# BITSv4.net
KiCad netlist of a schematic drawn in EAGLE
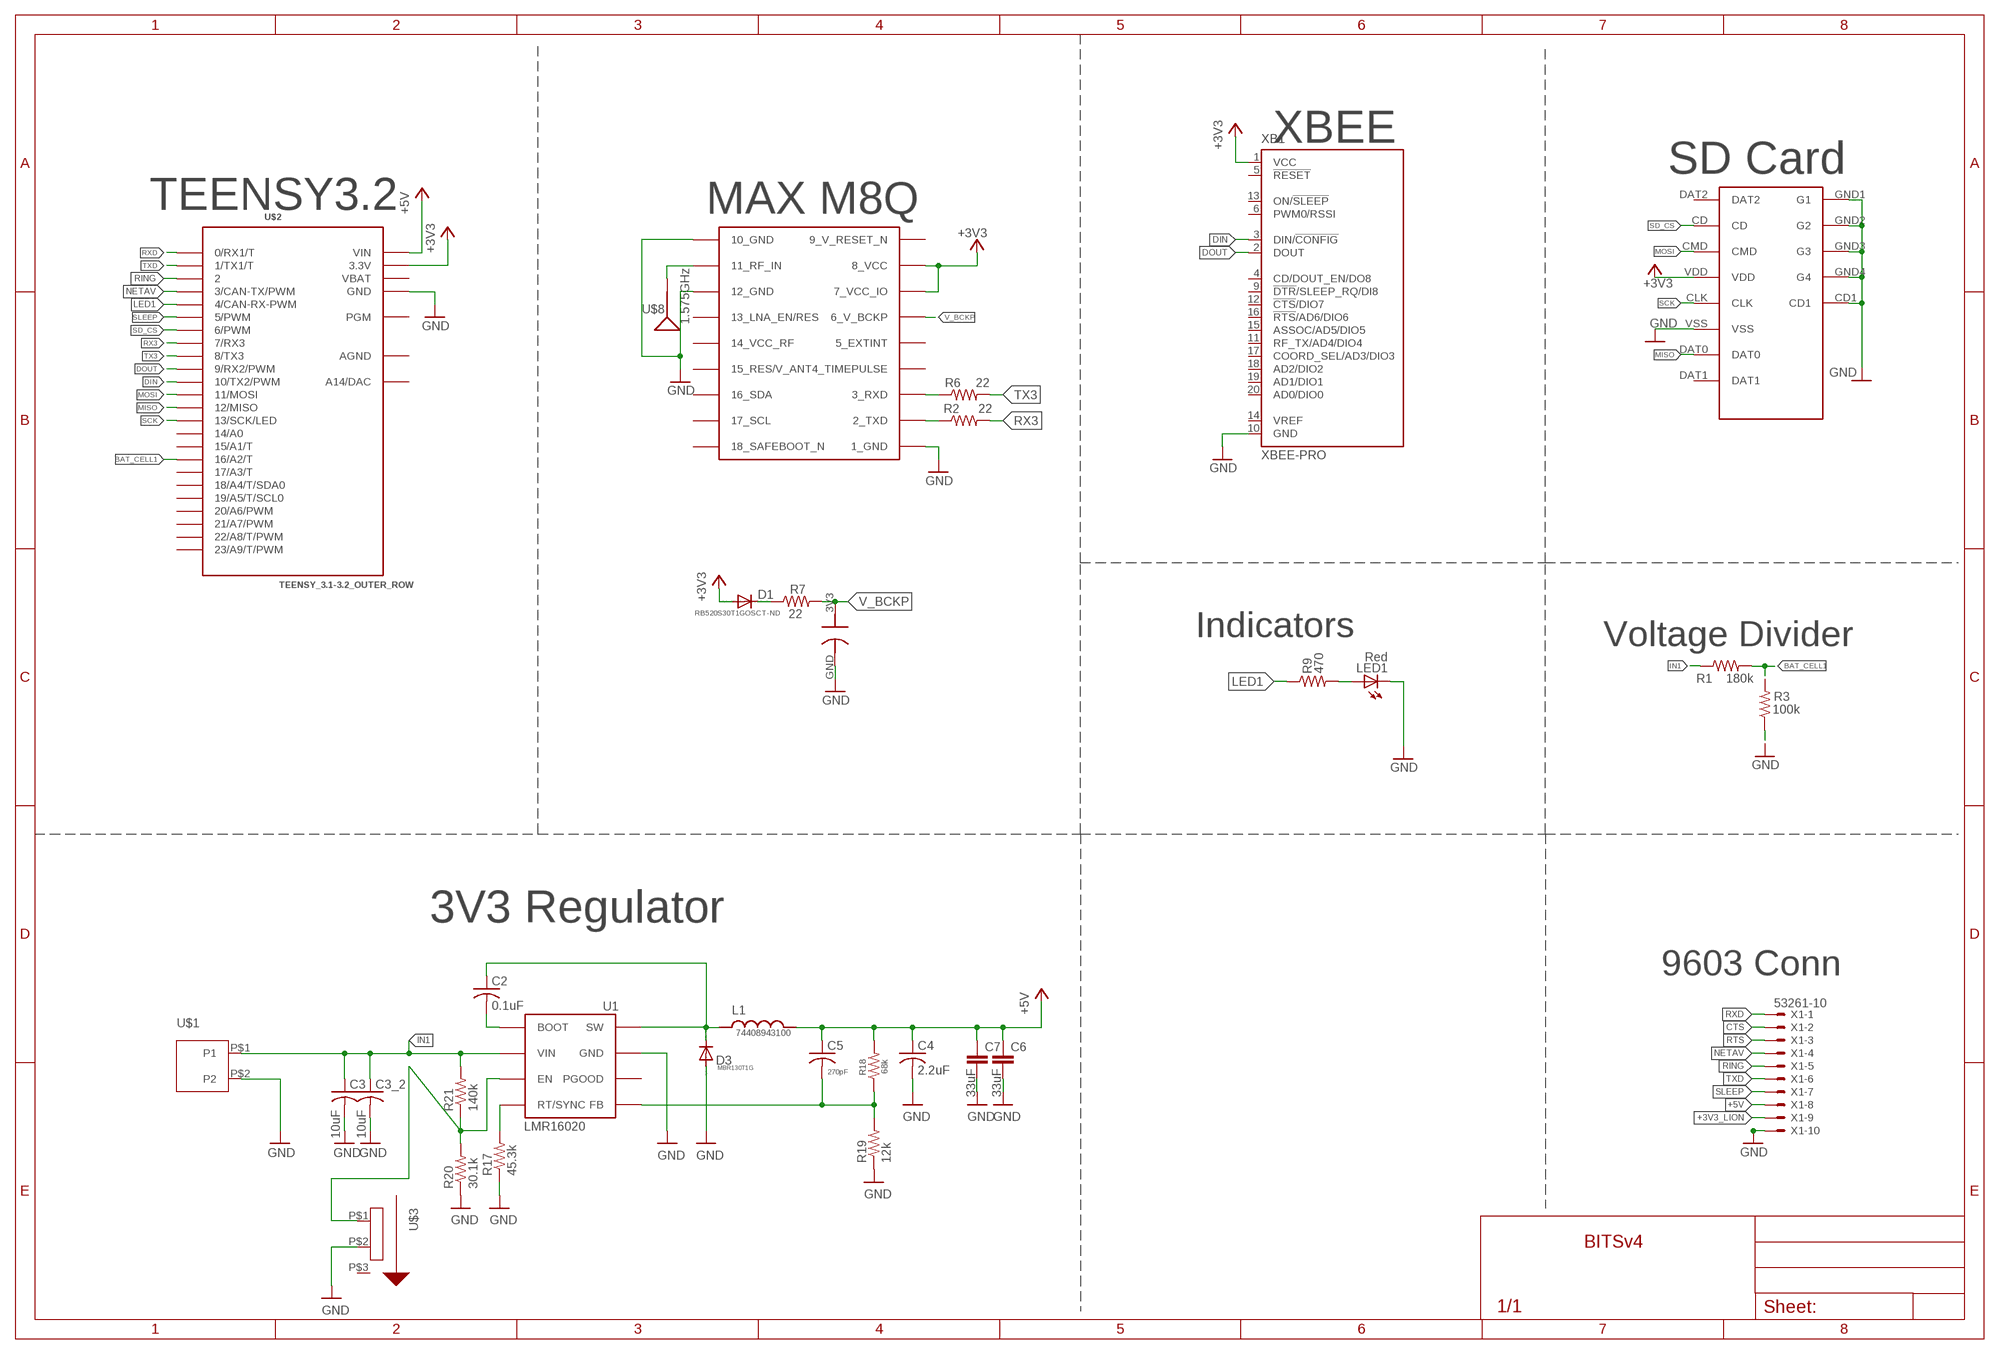
[diagram p0: schematic, sheet 1]

(export (version "E")
  (design (tool "Eeschema 10.0.6"))
  (components
    (comp (ref "C1")
      (value "0.2F")
      (footprint "eagle-import:ELNASUPERCAP")
      (libsource (lib "eagle-import") (part "DCK-3R3E204T614-E"))
    )
    (comp (ref "C2")
      (value "0.1uF")
      (footprint "eagle-import:C0603")
      (libsource (lib "eagle-import") (part "resistor_C-USC0603"))
    )
    (comp (ref "C3")
      (value "10uF")
      (footprint "eagle-import:C0805")
      (libsource (lib "eagle-import") (part "C-USC0805"))
    )
    (comp (ref "C3_2")
      (value "10uF")
      (footprint "eagle-import:C0805")
      (libsource (lib "eagle-import") (part "C-USC0805"))
    )
    (comp (ref "C4")
      (value "2.2uF")
      (footprint "eagle-import:C0603")
      (libsource (lib "eagle-import") (part "C-USC0603"))
    )
    (comp (ref "C5")
      (value "270pF")
      (footprint "eagle-import:C0402")
      (libsource (lib "eagle-import") (part "C-USC0402"))
    )
    (comp (ref "C6")
      (value "33uF")
      (footprint "eagle-import:C050-024X044")
      (libsource (lib "eagle-import") (part "C-EU050-024X044"))
    )
    (comp (ref "C7")
      (value "33uF")
      (footprint "eagle-import:C050-024X044")
      (libsource (lib "eagle-import") (part "C-EU050-024X044"))
    )
    (comp (ref "D1")
      (value "RB520S30T1GOSCT-ND")
      (footprint "eagle-import:SOD523")
      (libsource (lib "eagle-import") (part "DIODE-SOD523"))
    )
    (comp (ref "D3")
      (value "MBR130T1G")
      (footprint "eagle-import:SOD-123_MINI-SMA")
      (libsource (lib "eagle-import") (part "CGRM400-G1"))
    )
    (comp (ref "L1")
      (value "74408943100")
      (footprint "eagle-import:74408943100")
      (libsource (lib "eagle-import") (part "74408943100"))
    )
    (comp (ref "LED1")
      (value "Red")
      (footprint "eagle-import:CHIP-LED0603")
      (libsource (lib "eagle-import") (part "LEDCHIP-LED0603"))
    )
    (comp (ref "R1")
      (value "180k")
      (footprint "eagle-import:R0603")
      (libsource (lib "eagle-import") (part "resistor_R-US_R0603"))
    )
    (comp (ref "R2")
      (value "22")
      (footprint "eagle-import:R0603")
      (libsource (lib "eagle-import") (part "R-US_R0603"))
    )
    (comp (ref "R3")
      (value "100k")
      (footprint "eagle-import:R0603")
      (libsource (lib "eagle-import") (part "resistor_R-US_R0603"))
    )
    (comp (ref "R6")
      (value "22")
      (footprint "eagle-import:R0603")
      (libsource (lib "eagle-import") (part "R-US_R0603"))
    )
    (comp (ref "R7")
      (value "22")
      (footprint "eagle-import:R0603")
      (libsource (lib "eagle-import") (part "R-US_R0603"))
    )
    (comp (ref "R9")
      (value "470")
      (footprint "eagle-import:R0603")
      (libsource (lib "eagle-import") (part "resistor_R-US_R0603"))
    )
    (comp (ref "R17")
      (value "45.3k")
      (footprint "eagle-import:R0603")
      (libsource (lib "eagle-import") (part "resistor_R-US_R0603"))
    )
    (comp (ref "R18")
      (value "68k")
      (footprint "eagle-import:R0603")
      (libsource (lib "eagle-import") (part "resistor_R-US_R0603"))
    )
    (comp (ref "R19")
      (value "12k")
      (footprint "eagle-import:R0603")
      (libsource (lib "eagle-import") (part "resistor_R-US_R0603"))
    )
    (comp (ref "R20")
      (value "30.1k")
      (footprint "eagle-import:R0603")
      (libsource (lib "eagle-import") (part "resistor_R-US_R0603"))
    )
    (comp (ref "R21")
      (value "140k")
      (footprint "eagle-import:R0603")
      (libsource (lib "eagle-import") (part "resistor_R-US_R0603"))
    )
    (comp (ref "U$1")
      (value "559350210")
      (footprint "eagle-import:559350210")
      (libsource (lib "eagle-import") (part "559350210"))
    )
    (comp (ref "U$2")
      (value "TEENSY_3.1-3.2_OUTER_ROW")
      (footprint "eagle-import:TEENSY_3.0-3.2&LC_OUTER_ROW")
      (libsource (lib "eagle-import") (part "TEENSY_3.1-3.2_OUTER_ROW"))
    )
    (comp (ref "U$3")
      (value "CL-SB-12B-01")
      (footprint "eagle-import:CL-SB-12B-01")
      (libsource (lib "eagle-import") (part "CL-SB-12B-01"))
    )
    (comp (ref "U$4")
      (value "MICRO_SD")
      (footprint "eagle-import:MICRO_SD_HINGED")
      (libsource (lib "eagle-import") (part "MICRO_SD"))
    )
    (comp (ref "U$7")
      (value "MAX-M8")
      (footprint "eagle-import:MAX-M8")
      (libsource (lib "eagle-import") (part "MAX-M8"))
    )
    (comp (ref "U$8")
      (value "1.575GHz")
      (footprint "eagle-import:SPARKFUN-GPS_ANT-GPS-2X7MM")
      (libsource (lib "eagle-import") (part "SPARKFUN-GPS_ANTENNAGPS-2X7MM"))
    )
    (comp (ref "U1")
      (value "LMR16020")
      (footprint "eagle-import:SO8")
      (libsource (lib "eagle-import") (part "LMR16020"))
    )
    (comp (ref "X1")
      (value "53261-10")
      (footprint "eagle-import:53261-10")
      (fields (field (name "MF") "MOLEX"))
      (libsource (lib "eagle-import") (part "53?-10261"))
    )
    (comp (ref "XB1")
      (value "XBEE-PRO")
      (footprint "eagle-import:XBEE-PRO")
      (libsource (lib "eagle-import") (part "XBEE-PRO"))
    )
  )
  (nets
    (net (code "1") (name "+3V3") (class "Default")
      (node (ref "D1") (pin "A") (pinfunction "A_A") (pintype "passive"))
      (node (ref "U$2") (pin "3.3V") (pinfunction "3.3V_3.3V") (pintype "power_in"))
      (node (ref "U$2") (pin "3.3V1") (pinfunction "3.3V_3.3V1") (pintype "power_in"))
      (node (ref "U$4") (pin "VDD") (pinfunction "VDD_VDD") (pintype "bidirectional"))
      (node (ref "U$7") (pin "7_VCC_IO") (pinfunction "7_VCC_IO_7_VCC_IO") (pintype "power_in"))
      (node (ref "U$7") (pin "8_VCC") (pinfunction "8_VCC_8_VCC") (pintype "power_in"))
      (node (ref "XB1") (pin "1") (pinfunction "VCC_1") (pintype "power_in"))
    )
    (net (code "2") (name "+3V3_LION") (class "Default")
      (node (ref "X1") (pin "9") (pinfunction "S_9") (pintype "passive"))
    )
    (net (code "3") (name "+5V") (class "Default")
      (node (ref "C4") (pin "1") (pinfunction "1_1") (pintype "passive"))
      (node (ref "C5") (pin "1") (pinfunction "1_1") (pintype "passive"))
      (node (ref "C6") (pin "1") (pinfunction "1_1") (pintype "passive"))
      (node (ref "C7") (pin "1") (pinfunction "1_1") (pintype "passive"))
      (node (ref "L1") (pin "P$2") (pinfunction "P$2_P$2") (pintype "bidirectional"))
      (node (ref "R18") (pin "2") (pinfunction "2_2") (pintype "passive"))
      (node (ref "U$2") (pin "VIN") (pinfunction "VIN_VIN") (pintype "power_in"))
      (node (ref "X1") (pin "8") (pinfunction "S_8") (pintype "passive"))
    )
    (net (code "4") (name "/9_V_RESET_N") (class "Default")
      (node (ref "U$7") (pin "9_RESET_N") (pinfunction "9_V_RESET_N_9_RESET_N") (pintype "power_in"))
    )
    (net (code "5") (name "/AGND") (class "Default")
      (node (ref "U$2") (pin "AGND") (pinfunction "AGND_AGND") (pintype "power_in"))
    )
    (net (code "6") (name "/VBAT") (class "Default")
      (node (ref "U$2") (pin "VBAT") (pinfunction "VBAT_VBAT") (pintype "power_in"))
    )
    (net (code "7") (name "BAT_CELL1") (class "Default")
      (node (ref "R1") (pin "2") (pinfunction "2_2") (pintype "passive"))
      (node (ref "R3") (pin "2") (pinfunction "2_2") (pintype "passive"))
      (node (ref "U$2") (pin "16/A2") (pinfunction "16/A2/T_16/A2") (pintype "bidirectional"))
    )
    (net (code "8") (name "CTS") (class "Default")
      (node (ref "X1") (pin "2") (pinfunction "S_2") (pintype "passive"))
    )
    (net (code "9") (name "DIN") (class "Default")
      (node (ref "U$2") (pin "10") (pinfunction "10/TX2/PWM_10") (pintype "bidirectional"))
      (node (ref "XB1") (pin "3") (pinfunction "DIN/~{CONFIG}_3") (pintype "input"))
    )
    (net (code "10") (name "DOUT") (class "Default")
      (node (ref "U$2") (pin "9") (pinfunction "9/RX2/PWM_9") (pintype "bidirectional"))
      (node (ref "XB1") (pin "2") (pinfunction "DOUT_2") (pintype "output"))
    )
    (net (code "11") (name "GND") (class "Default")
      (node (ref "C1") (pin "GND") (pinfunction "GND_GND") (pintype "bidirectional"))
      (node (ref "C3") (pin "2") (pinfunction "2_2") (pintype "passive"))
      (node (ref "C3_2") (pin "2") (pinfunction "2_2") (pintype "passive"))
      (node (ref "C4") (pin "2") (pinfunction "2_2") (pintype "passive"))
      (node (ref "C6") (pin "2") (pinfunction "2_2") (pintype "passive"))
      (node (ref "C7") (pin "2") (pinfunction "2_2") (pintype "passive"))
      (node (ref "D3") (pin "A") (pinfunction "A_A") (pintype "passive"))
      (node (ref "LED1") (pin "C") (pinfunction "C_C") (pintype "passive"))
      (node (ref "R17") (pin "1") (pinfunction "1_1") (pintype "passive"))
      (node (ref "R19") (pin "1") (pinfunction "1_1") (pintype "passive"))
      (node (ref "R20") (pin "1") (pinfunction "1_1") (pintype "passive"))
      (node (ref "R3") (pin "1") (pinfunction "1_1") (pintype "passive"))
      (node (ref "U$1") (pin "P$2") (pinfunction "P2_P$2") (pintype "bidirectional"))
      (node (ref "U$2") (pin "GND") (pinfunction "GND_GND") (pintype "power_in"))
      (node (ref "U$2") (pin "GND1") (pinfunction "GND_GND1") (pintype "power_in"))
      (node (ref "U$3") (pin "P$2") (pinfunction "P2_P$2") (pintype "bidirectional"))
      (node (ref "U$4") (pin "CD1") (pinfunction "CD1_CD1") (pintype "bidirectional"))
      (node (ref "U$4") (pin "GND1") (pinfunction "G1_GND1") (pintype "bidirectional"))
      (node (ref "U$4") (pin "GND2") (pinfunction "G2_GND2") (pintype "bidirectional"))
      (node (ref "U$4") (pin "GND3") (pinfunction "G3_GND3") (pintype "bidirectional"))
      (node (ref "U$4") (pin "GND4") (pinfunction "G4_GND4") (pintype "bidirectional"))
      (node (ref "U$4") (pin "VSS") (pinfunction "VSS_VSS") (pintype "bidirectional"))
      (node (ref "U$7") (pin "10_GND") (pinfunction "10_GND_10_GND") (pintype "power_in"))
      (node (ref "U$7") (pin "12_GND") (pinfunction "12_GND_12_GND") (pintype "power_in"))
      (node (ref "U$7") (pin "1_GND") (pinfunction "1_GND_1_GND") (pintype "power_in"))
      (node (ref "U1") (pin "P$7") (pinfunction "GND_P$7") (pintype "bidirectional"))
      (node (ref "U1") (pin "PAD") (pinfunction "GND_PAD") (pintype "bidirectional"))
      (node (ref "X1") (pin "10") (pinfunction "S_10") (pintype "passive"))
      (node (ref "XB1") (pin "10") (pinfunction "GND_10") (pintype "power_in"))
    )
    (net (code "12") (name "IN1") (class "Default")
      (node (ref "C3") (pin "1") (pinfunction "1_1") (pintype "passive"))
      (node (ref "C3_2") (pin "1") (pinfunction "1_1") (pintype "passive"))
      (node (ref "R1") (pin "1") (pinfunction "1_1") (pintype "passive"))
      (node (ref "R21") (pin "2") (pinfunction "2_2") (pintype "passive"))
      (node (ref "U$1") (pin "P$1") (pinfunction "P1_P$1") (pintype "bidirectional"))
      (node (ref "U1") (pin "P$2") (pinfunction "VIN_P$2") (pintype "bidirectional"))
    )
    (net (code "13") (name "LED1") (class "Default")
      (node (ref "R9") (pin "1") (pinfunction "1_1") (pintype "passive"))
      (node (ref "U$2") (pin "4") (pinfunction "4/CAN-RX-PWM_4") (pintype "bidirectional"))
    )
    (net (code "14") (name "MISO") (class "Default")
      (node (ref "U$2") (pin "12") (pinfunction "12/MISO_12") (pintype "bidirectional"))
      (node (ref "U$4") (pin "DAT0") (pinfunction "DAT0_DAT0") (pintype "bidirectional"))
    )
    (net (code "15") (name "MOSI") (class "Default")
      (node (ref "U$2") (pin "11") (pinfunction "11/MOSI_11") (pintype "bidirectional"))
      (node (ref "U$4") (pin "CMD") (pinfunction "CMD_CMD") (pintype "bidirectional"))
    )
    (net (code "16") (name "NETAV") (class "Default")
      (node (ref "U$2") (pin "3") (pinfunction "3/CAN-TX/PWM_3") (pintype "bidirectional"))
      (node (ref "X1") (pin "4") (pinfunction "S_4") (pintype "passive"))
    )
    (net (code "17") (name "Net-(D1-PadC)") (class "Default")
      (node (ref "D1") (pin "C") (pinfunction "C_C") (pintype "passive"))
      (node (ref "R7") (pin "1") (pinfunction "1_1") (pintype "passive"))
    )
    (net (code "18") (name "Net-(LED1-PadA)") (class "Default")
      (node (ref "LED1") (pin "A") (pinfunction "A_A") (pintype "passive"))
      (node (ref "R9") (pin "2") (pinfunction "2_2") (pintype "passive"))
    )
    (net (code "19") (name "Net-(R2-Pad1)") (class "Default")
      (node (ref "R2") (pin "1") (pinfunction "1_1") (pintype "passive"))
      (node (ref "U$7") (pin "2_TXD") (pinfunction "2_TXD_2_TXD") (pintype "bidirectional"))
    )
    (net (code "20") (name "Net-(R6-Pad1)") (class "Default")
      (node (ref "R6") (pin "1") (pinfunction "1_1") (pintype "passive"))
      (node (ref "U$7") (pin "3_RXD") (pinfunction "3_RXD_3_RXD") (pintype "bidirectional"))
    )
    (net (code "21") (name "Net-(U$3-P1)") (class "Default")
      (node (ref "R20") (pin "2") (pinfunction "2_2") (pintype "passive"))
      (node (ref "R21") (pin "1") (pinfunction "1_1") (pintype "passive"))
      (node (ref "U$3") (pin "P$1") (pinfunction "P1_P$1") (pintype "bidirectional"))
      (node (ref "U1") (pin "P$3") (pinfunction "EN_P$3") (pintype "bidirectional"))
    )
    (net (code "22") (name "Net-(U$8-SIGNAL)") (class "Default")
      (node (ref "U$7") (pin "11_RF_IN") (pinfunction "11_RF_IN_11_RF_IN") (pintype "bidirectional"))
      (node (ref "U$8") (pin "1") (pinfunction "SIGNAL_1") (pintype "bidirectional"))
    )
    (net (code "23") (name "Net-(U1-BOOT)") (class "Default")
      (node (ref "C2") (pin "2") (pinfunction "2_2") (pintype "passive"))
      (node (ref "U1") (pin "P$1") (pinfunction "BOOT_P$1") (pintype "bidirectional"))
    )
    (net (code "24") (name "Net-(U1-FB)") (class "Default")
      (node (ref "C5") (pin "2") (pinfunction "2_2") (pintype "passive"))
      (node (ref "R18") (pin "1") (pinfunction "1_1") (pintype "passive"))
      (node (ref "R19") (pin "2") (pinfunction "2_2") (pintype "passive"))
      (node (ref "U1") (pin "P$5") (pinfunction "FB_P$5") (pintype "bidirectional"))
    )
    (net (code "25") (name "Net-(U1-RT{slash}SYNC)") (class "Default")
      (node (ref "R17") (pin "2") (pinfunction "2_2") (pintype "passive"))
      (node (ref "U1") (pin "P$4") (pinfunction "RT/SYNC_P$4") (pintype "bidirectional"))
    )
    (net (code "26") (name "Net-(U1-SW)") (class "Default")
      (node (ref "C2") (pin "1") (pinfunction "1_1") (pintype "passive"))
      (node (ref "D3") (pin "C") (pinfunction "C_C") (pintype "passive"))
      (node (ref "L1") (pin "P$1") (pinfunction "P$1_P$1") (pintype "bidirectional"))
      (node (ref "U1") (pin "P$8") (pinfunction "SW_P$8") (pintype "bidirectional"))
    )
    (net (code "27") (name "RING") (class "Default")
      (node (ref "U$2") (pin "2") (pinfunction "2_2") (pintype "bidirectional"))
      (node (ref "X1") (pin "5") (pinfunction "S_5") (pintype "passive"))
    )
    (net (code "28") (name "RTS") (class "Default")
      (node (ref "X1") (pin "3") (pinfunction "S_3") (pintype "passive"))
    )
    (net (code "29") (name "RX3") (class "Default")
      (node (ref "R2") (pin "2") (pinfunction "2_2") (pintype "passive"))
      (node (ref "U$2") (pin "7") (pinfunction "7/RX3_7") (pintype "bidirectional"))
    )
    (net (code "30") (name "RXD") (class "Default")
      (node (ref "U$2") (pin "0") (pinfunction "0/RX1/T_0") (pintype "bidirectional"))
      (node (ref "X1") (pin "1") (pinfunction "S_1") (pintype "passive"))
    )
    (net (code "31") (name "SCK") (class "Default")
      (node (ref "U$2") (pin "13") (pinfunction "13/SCK/LED_13") (pintype "bidirectional"))
      (node (ref "U$4") (pin "CLK") (pinfunction "CLK_CLK") (pintype "bidirectional"))
    )
    (net (code "32") (name "SD_CS") (class "Default")
      (node (ref "U$2") (pin "6") (pinfunction "6/PWM_6") (pintype "bidirectional"))
      (node (ref "U$4") (pin "CD") (pinfunction "CD_CD") (pintype "bidirectional"))
    )
    (net (code "33") (name "SLEEP") (class "Default")
      (node (ref "U$2") (pin "5") (pinfunction "5/PWM_5") (pintype "bidirectional"))
      (node (ref "X1") (pin "7") (pinfunction "S_7") (pintype "passive"))
    )
    (net (code "34") (name "TX3") (class "Default")
      (node (ref "R6") (pin "2") (pinfunction "2_2") (pintype "passive"))
      (node (ref "U$2") (pin "8") (pinfunction "8/TX3_8") (pintype "bidirectional"))
    )
    (net (code "35") (name "TXD") (class "Default")
      (node (ref "U$2") (pin "1") (pinfunction "1/TX1/T_1") (pintype "bidirectional"))
      (node (ref "X1") (pin "6") (pinfunction "S_6") (pintype "passive"))
    )
    (net (code "36") (name "V_BCKP") (class "Default")
      (node (ref "C1") (pin "3V3") (pinfunction "3V3_3V3") (pintype "bidirectional"))
      (node (ref "R7") (pin "2") (pinfunction "2_2") (pintype "passive"))
      (node (ref "U$7") (pin "6_V_BCKP") (pinfunction "6_V_BCKP_6_V_BCKP") (pintype "bidirectional"))
    )
    (net (code "37") (name "unconnected-(U$2-15{slash}A1{slash}T-Pad15{slash}A1)") (class "Default")
      (node (ref "U$2") (pin "15/A1") (pinfunction "15/A1/T_15/A1") (pintype "bidirectional"))
    )
    (net (code "38") (name "unconnected-(U$2-17{slash}A3{slash}T-Pad17{slash}A3)") (class "Default")
      (node (ref "U$2") (pin "17/A3") (pinfunction "17/A3/T_17/A3") (pintype "bidirectional"))
    )
    (net (code "39") (name "unconnected-(U$2-18{slash}A4{slash}T{slash}SDA0-Pad18{slash}A4)") (class "Default")
      (node (ref "U$2") (pin "18/A4") (pinfunction "18/A4/T/SDA0_18/A4") (pintype "bidirectional"))
    )
    (net (code "40") (name "unconnected-(U$2-19{slash}A5{slash}T{slash}SCL0-Pad19{slash}A5)") (class "Default")
      (node (ref "U$2") (pin "19/A5") (pinfunction "19/A5/T/SCL0_19/A5") (pintype "bidirectional"))
    )
    (net (code "41") (name "unconnected-(U$2-20{slash}A6{slash}PWM-Pad20{slash}A6)") (class "Default")
      (node (ref "U$2") (pin "20/A6") (pinfunction "20/A6/PWM_20/A6") (pintype "bidirectional"))
    )
    (net (code "42") (name "unconnected-(U$2-21{slash}A7{slash}PWM-Pad21{slash}A7)") (class "Default")
      (node (ref "U$2") (pin "21/A7") (pinfunction "21/A7/PWM_21/A7") (pintype "bidirectional"))
    )
    (net (code "43") (name "unconnected-(U$2-22{slash}A8{slash}T{slash}PWM-Pad22{slash}A8)") (class "Default")
      (node (ref "U$2") (pin "22/A8") (pinfunction "22/A8/T/PWM_22/A8") (pintype "bidirectional"))
    )
    (net (code "44") (name "unconnected-(U$2-23{slash}A9{slash}T{slash}PWM-Pad23{slash}A9)") (class "Default")
      (node (ref "U$2") (pin "23/A9") (pinfunction "23/A9/T/PWM_23/A9") (pintype "bidirectional"))
    )
    (net (code "45") (name "unconnected-(U$2-A14{slash}DAC-PadRESET{slash}DAC)") (class "Default")
      (node (ref "U$2") (pin "RESET/DAC") (pinfunction "A14/DAC_RESET/DAC") (pintype "bidirectional"))
    )
    (net (code "46") (name "unconnected-(U$2-Pad14{slash}A0)") (class "Default")
      (node (ref "U$2") (pin "14/A0") (pinfunction "14/A0_14/A0") (pintype "bidirectional"))
    )
    (net (code "47") (name "unconnected-(U$2-PadPGM)") (class "Default")
      (node (ref "U$2") (pin "PGM") (pinfunction "PGM_PGM") (pintype "bidirectional"))
    )
    (net (code "48") (name "unconnected-(U$3-P3-PadP$3)") (class "Default")
      (node (ref "U$3") (pin "P$3") (pinfunction "P3_P$3") (pintype "bidirectional"))
    )
    (net (code "49") (name "unconnected-(U$4-PadDAT1)") (class "Default")
      (node (ref "U$4") (pin "DAT1") (pinfunction "DAT1_DAT1") (pintype "bidirectional"))
    )
    (net (code "50") (name "unconnected-(U$4-PadDAT2)") (class "Default")
      (node (ref "U$4") (pin "DAT2") (pinfunction "DAT2_DAT2") (pintype "bidirectional"))
    )
    (net (code "51") (name "unconnected-(U$7-13_LNA_EN{slash}RES-Pad13_LNA_EN)") (class "Default")
      (node (ref "U$7") (pin "13_LNA_EN") (pinfunction "13_LNA_EN/RES_13_LNA_EN") (pintype "bidirectional"))
    )
    (net (code "52") (name "unconnected-(U$7-15_RES{slash}V_ANT-Pad15_V_ANT{slash}RESERVED)") (class "Default")
      (node (ref "U$7") (pin "15_V_ANT/RESERVED") (pinfunction "15_RES/V_ANT_15_V_ANT/RESERVED") (pintype "bidirectional"))
    )
    (net (code "53") (name "unconnected-(U$7-Pad4_TIMEPULSE)") (class "Default")
      (node (ref "U$7") (pin "4_TIMEPULSE") (pinfunction "4_TIMEPULSE_4_TIMEPULSE") (pintype "bidirectional"))
    )
    (net (code "54") (name "unconnected-(U$7-Pad5_EXTINT)") (class "Default")
      (node (ref "U$7") (pin "5_EXTINT") (pinfunction "5_EXTINT_5_EXTINT") (pintype "bidirectional"))
    )
    (net (code "55") (name "unconnected-(U$7-Pad14_VCC_RF)") (class "Default")
      (node (ref "U$7") (pin "14_VCC_RF") (pinfunction "14_VCC_RF_14_VCC_RF") (pintype "bidirectional"))
    )
    (net (code "56") (name "unconnected-(U$7-Pad16_SDA)") (class "Default")
      (node (ref "U$7") (pin "16_SDA") (pinfunction "16_SDA_16_SDA") (pintype "bidirectional"))
    )
    (net (code "57") (name "unconnected-(U$7-Pad17_SCL)") (class "Default")
      (node (ref "U$7") (pin "17_SCL") (pinfunction "17_SCL_17_SCL") (pintype "bidirectional"))
    )
    (net (code "58") (name "unconnected-(U$7-Pad18_SAFEBOOT_N)") (class "Default")
      (node (ref "U$7") (pin "18_SAFEBOOT_N") (pinfunction "18_SAFEBOOT_N_18_SAFEBOOT_N") (pintype "bidirectional"))
    )
    (net (code "59") (name "unconnected-(U1-PGOOD-PadP$6)") (class "Default")
      (node (ref "U1") (pin "P$6") (pinfunction "PGOOD_P$6") (pintype "bidirectional"))
    )
    (net (code "60") (name "unconnected-(XB1-AD0{slash}DIO0-Pad20)") (class "Default")
      (node (ref "XB1") (pin "20") (pinfunction "AD0/DIO0_20") (pintype "bidirectional"))
    )
    (net (code "61") (name "unconnected-(XB1-AD1{slash}DIO1-Pad19)") (class "Default")
      (node (ref "XB1") (pin "19") (pinfunction "AD1/DIO1_19") (pintype "bidirectional"))
    )
    (net (code "62") (name "unconnected-(XB1-AD2{slash}DIO2-Pad18)") (class "Default")
      (node (ref "XB1") (pin "18") (pinfunction "AD2/DIO2_18") (pintype "bidirectional"))
    )
    (net (code "63") (name "unconnected-(XB1-ASSOC{slash}AD5{slash}DIO5-Pad15)") (class "Default")
      (node (ref "XB1") (pin "15") (pinfunction "ASSOC/AD5/DIO5_15") (pintype "bidirectional"))
    )
    (net (code "64") (name "unconnected-(XB1-CD{slash}DOUT_EN{slash}DO8-Pad4)") (class "Default")
      (node (ref "XB1") (pin "4") (pinfunction "CD/DOUT_EN/DO8_4") (pintype "output"))
    )
    (net (code "65") (name "unconnected-(XB1-COORD_SEL{slash}AD3{slash}DIO3-Pad17)") (class "Default")
      (node (ref "XB1") (pin "17") (pinfunction "COORD_SEL/AD3/DIO3_17") (pintype "bidirectional"))
    )
    (net (code "66") (name "unconnected-(XB1-ON{slash}~{SLEEP}-Pad13)") (class "Default")
      (node (ref "XB1") (pin "13") (pinfunction "ON/~{SLEEP}_13") (pintype "output"))
    )
    (net (code "67") (name "unconnected-(XB1-PWM0{slash}RSSI-Pad6)") (class "Default")
      (node (ref "XB1") (pin "6") (pinfunction "PWM0/RSSI_6") (pintype "output"))
    )
    (net (code "68") (name "unconnected-(XB1-RF_TX{slash}AD4{slash}DIO4-Pad11)") (class "Default")
      (node (ref "XB1") (pin "11") (pinfunction "RF_TX/AD4/DIO4_11") (pintype "bidirectional"))
    )
    (net (code "69") (name "unconnected-(XB1-VREF-Pad14)") (class "Default")
      (node (ref "XB1") (pin "14") (pinfunction "VREF_14") (pintype "input"))
    )
    (net (code "70") (name "unconnected-(XB1-~{CTS}{slash}DIO7-Pad12)") (class "Default")
      (node (ref "XB1") (pin "12") (pinfunction "~{CTS}/DIO7_12") (pintype "bidirectional"))
    )
    (net (code "71") (name "unconnected-(XB1-~{DTR}{slash}SLEEP_RQ{slash}DI8-Pad9)") (class "Default")
      (node (ref "XB1") (pin "9") (pinfunction "~{DTR}/SLEEP_RQ/DI8_9") (pintype "bidirectional"))
    )
    (net (code "72") (name "unconnected-(XB1-~{RESET}-Pad5)") (class "Default")
      (node (ref "XB1") (pin "5") (pinfunction "~{RESET}_5") (pintype "input"))
    )
    (net (code "73") (name "unconnected-(XB1-~{RTS}{slash}AD6{slash}DIO6-Pad16)") (class "Default")
      (node (ref "XB1") (pin "16") (pinfunction "~{RTS}/AD6/DIO6_16") (pintype "bidirectional"))
    )
  )
)
